# -STM32F1.net
KiCad netlist of a schematic drawn in EasyEDA Pro
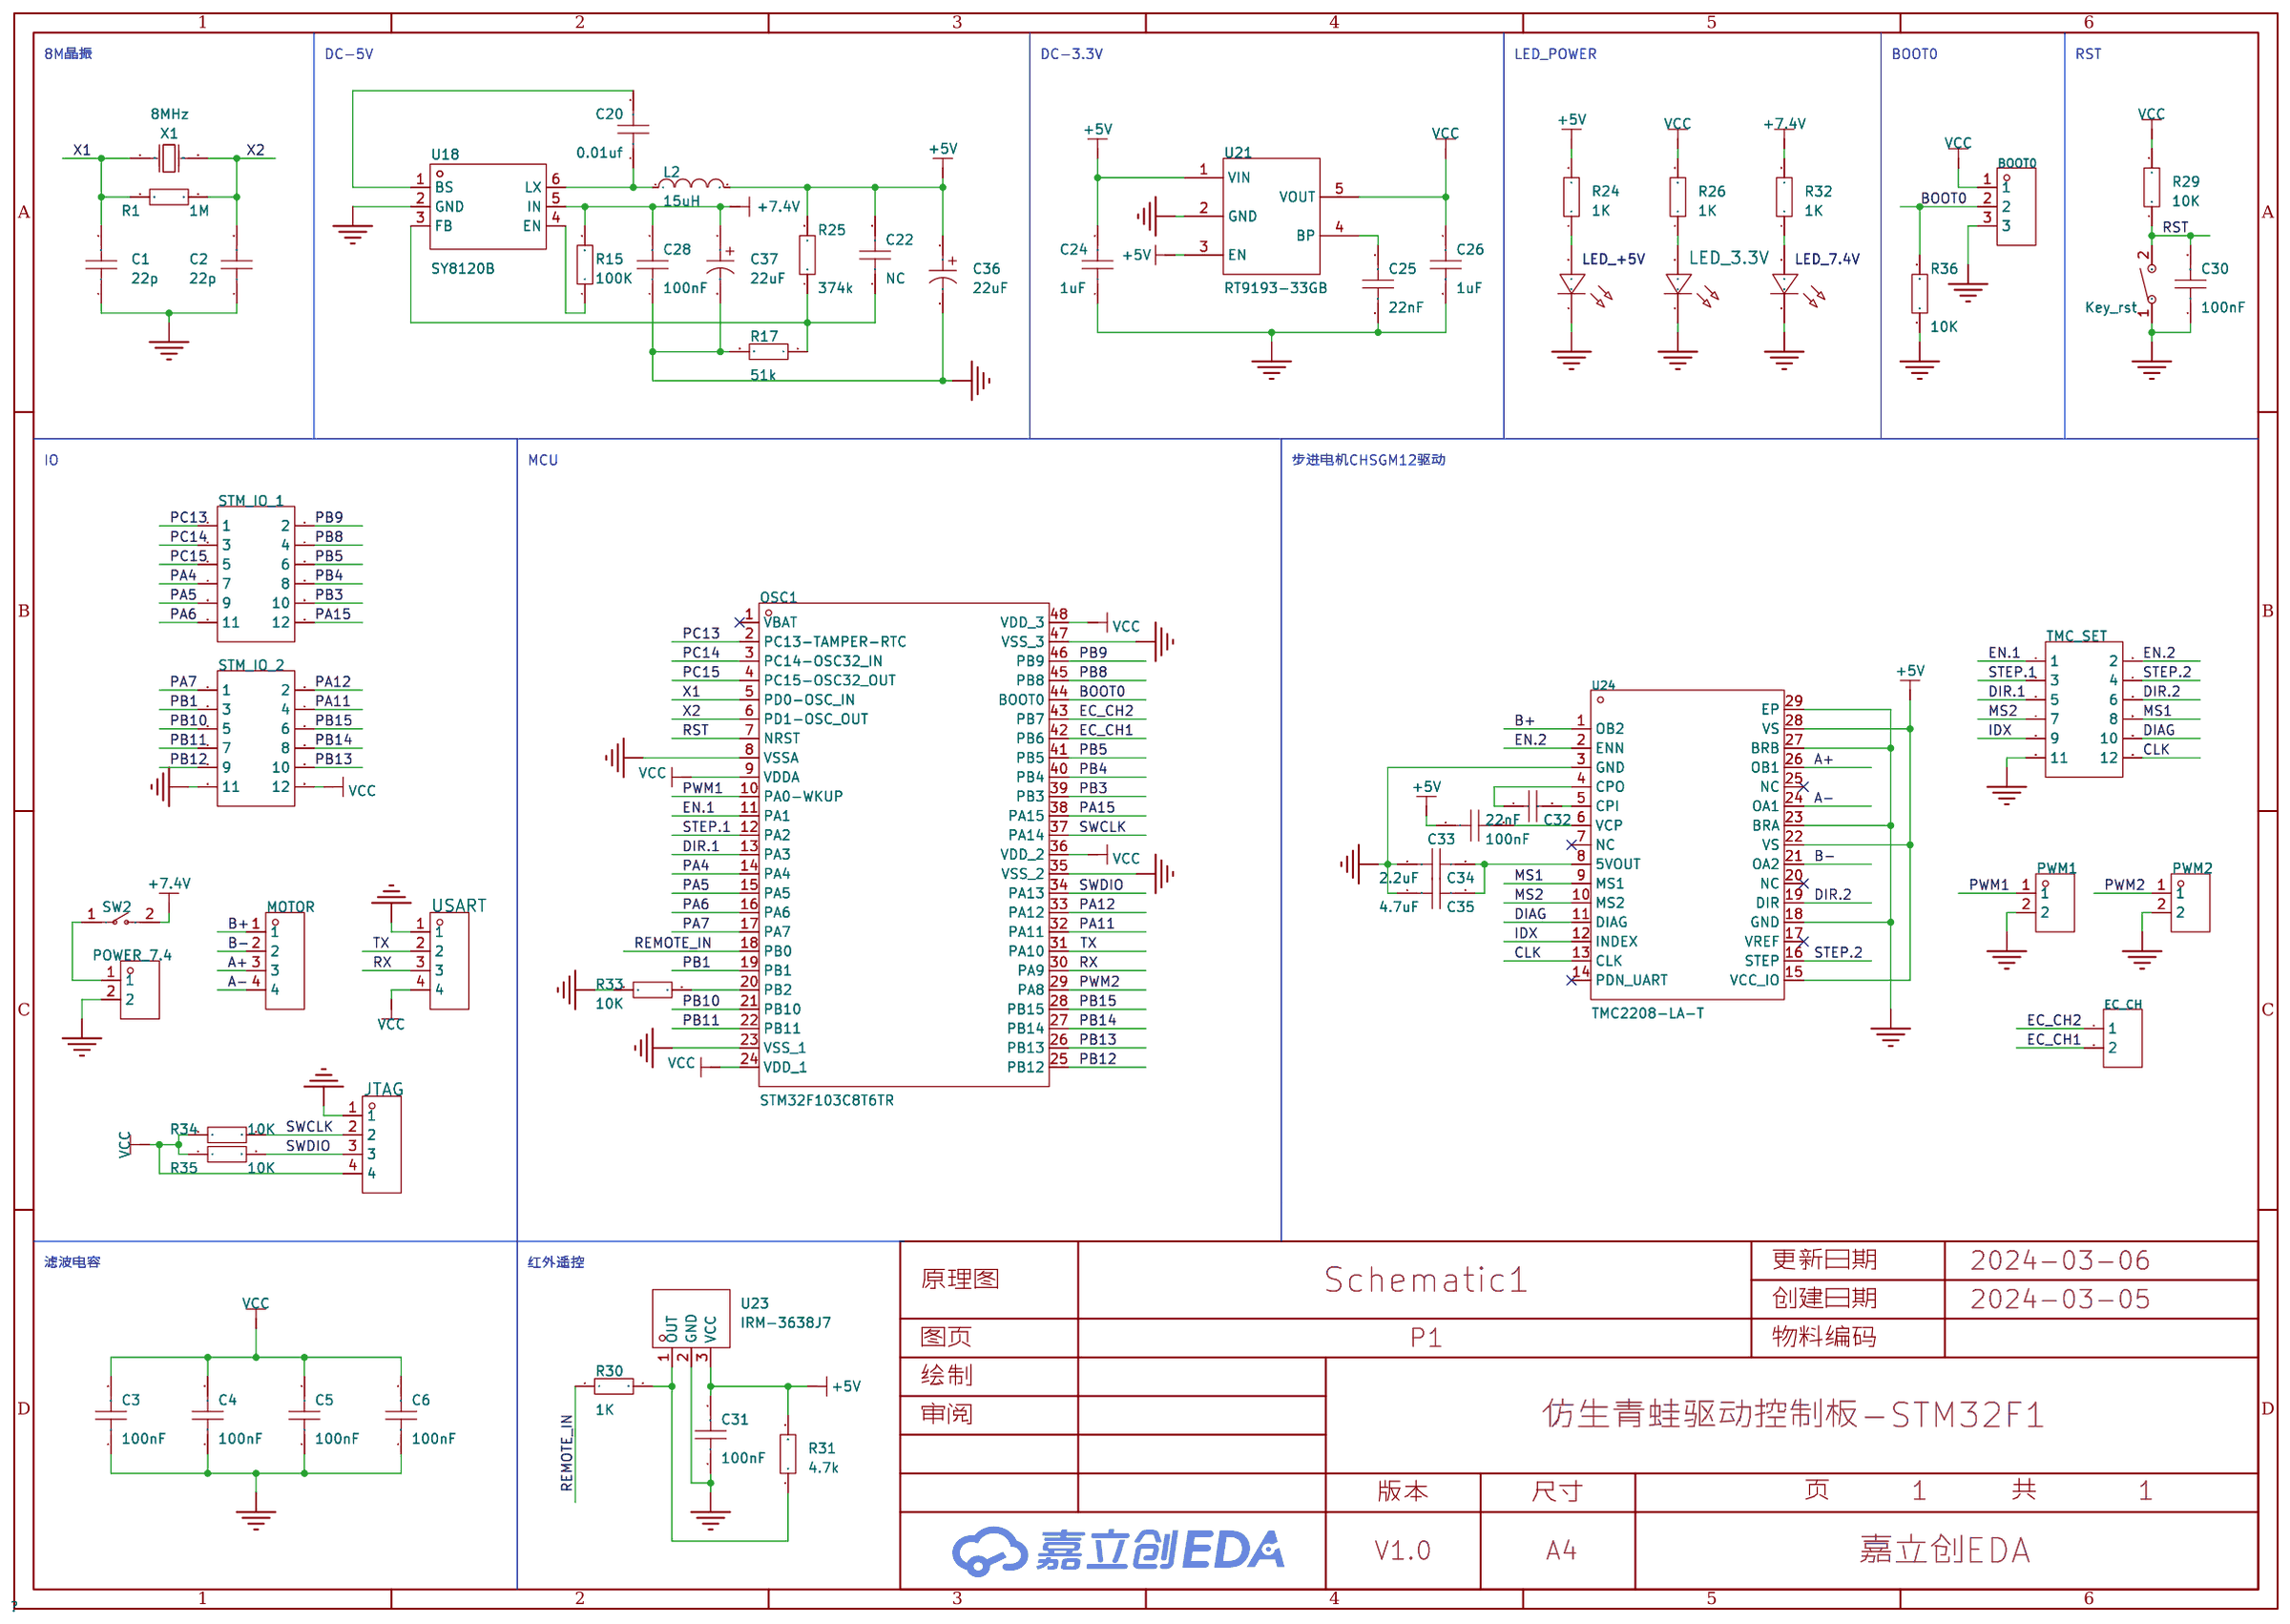
[diagram p0: schematic sheet]

(export (version "E")
  (design (tool "Eeschema 10.0.6"))
  (components
    (comp (ref "BOOT0")
      (value "~")
      (footprint "easyedapro:HDR-TH_3P-P2.54-V-F")
      (libsource (lib "easyedapro") (part "PM254V-11-03-H85"))
    )
    (comp (ref "C1")
      (value "22p")
      (footprint "easyedapro:c0603")
      (libsource (lib "easyedapro") (part "CapAcitance"))
    )
    (comp (ref "C2")
      (value "22p")
      (footprint "easyedapro:c0603")
      (libsource (lib "easyedapro") (part "CapAcitance"))
    )
    (comp (ref "C3")
      (value "100nF")
      (footprint "easyedapro:c0603")
      (libsource (lib "easyedapro") (part "CapAcitance"))
    )
    (comp (ref "C4")
      (value "100nF")
      (footprint "easyedapro:c0603")
      (libsource (lib "easyedapro") (part "CapAcitance"))
    )
    (comp (ref "C5")
      (value "100nF")
      (footprint "easyedapro:c0603")
      (libsource (lib "easyedapro") (part "CapAcitance"))
    )
    (comp (ref "C6")
      (value "100nF")
      (footprint "easyedapro:c0603")
      (libsource (lib "easyedapro") (part "CapAcitance"))
    )
    (comp (ref "C20")
      (value "0.01uf")
      (footprint "easyedapro:C0805")
      (libsource (lib "easyedapro") (part "CapAcitance"))
    )
    (comp (ref "C22")
      (value "NC")
      (footprint "easyedapro:C0805")
      (libsource (lib "easyedapro") (part "CapAcitance"))
    )
    (comp (ref "C24")
      (value "1uF")
      (footprint "easyedapro:c0603")
      (libsource (lib "easyedapro") (part "CapAcitance"))
    )
    (comp (ref "C25")
      (value "22nF")
      (footprint "easyedapro:c0603")
      (libsource (lib "easyedapro") (part "CapAcitance"))
    )
    (comp (ref "C26")
      (value "1uF")
      (footprint "easyedapro:c0603")
      (libsource (lib "easyedapro") (part "CapAcitance"))
    )
    (comp (ref "C28")
      (value "100nF")
      (footprint "easyedapro:c0603")
      (libsource (lib "easyedapro") (part "CapAcitance"))
    )
    (comp (ref "C30")
      (value "100nF")
      (footprint "easyedapro:c0603")
      (libsource (lib "easyedapro") (part "CapAcitance"))
    )
    (comp (ref "C31")
      (value "100nF")
      (footprint "easyedapro:c0603")
      (libsource (lib "easyedapro") (part "CapAcitance"))
    )
    (comp (ref "C32")
      (value "22nF")
      (footprint "easyedapro:c0603")
      (description "容值:22nF;精度:±10%;额定电压:50V;材质(温度系数):X7R;")
      (fields (field (name "Manufacturer Part") "0603B223K500NT") (field (name "Manufacturer") "FH(风华)"))
      (libsource (lib "easyedapro") (part "0603B223K500NT"))
    )
    (comp (ref "C33")
      (value "100nF")
      (footprint "easyedapro:c0603")
      (libsource (lib "easyedapro") (part "CapAcitance"))
    )
    (comp (ref "C34")
      (value "2.2uF")
      (footprint "easyedapro:c0603")
      (libsource (lib "easyedapro") (part "CapAcitance"))
    )
    (comp (ref "C35")
      (value "4.7uF")
      (footprint "easyedapro:c0603")
      (libsource (lib "easyedapro") (part "CapAcitance"))
    )
    (comp (ref "C36")
      (value "22uF")
      (footprint "easyedapro:CAP-SMD_BD5.0-L5.3-W5.3-LS6.0-FD")
      (description "容值:22uF;精度:±20%;额定电压:25V;纹波电流:26mA@120Hz;等效串联电阻:-;")
      (fields
        (field (name "Manufacturer Part") "RVT22UF25V67RV0047")
        (field (name "Manufacturer") "KNSCHA(科尼盛)")
      )
      (libsource (lib "easyedapro") (part "RVT22UF25V67RV0047"))
    )
    (comp (ref "C37")
      (value "22uF")
      (footprint "easyedapro:CAP-SMD_BD5.0-L5.3-W5.3-LS6.0-FD")
      (description "容值:22uF;精度:±20%;额定电压:25V;纹波电流:26mA@120Hz;等效串联电阻:-;")
      (fields
        (field (name "Manufacturer Part") "RVT22UF25V67RV0047")
        (field (name "Manufacturer") "KNSCHA(科尼盛)")
      )
      (libsource (lib "easyedapro") (part "RVT22UF25V67RV0047"))
    )
    (comp (ref "EC_CH")
      (value "~")
      (footprint "easyedapro:HDR-TH_2P-P2.54-V-F")
      (libsource (lib "easyedapro") (part "Header-Female-2.54_1x2"))
    )
    (comp (ref "JTAG")
      (value "~")
      (footprint "easyedapro:HDR-TH_4P-P2.54-V-F")
      (libsource (lib "easyedapro") (part "2.54-1*4P母"))
    )
    (comp (ref "Key_rst")
      (value "TS-1092S-B3D2-G")
      (footprint "easyedapro:SW-SMD_L6.1-W3.6-LS7.9")
      (description "电路结构:单刀单掷;按钮形状:矩形按钮;作用力:250gf;安装方式:立贴;开关长度:6.1mm;开关宽度:3.6mm;开关高度:2.5mm;带支架:不带;机械寿命:-;")
      (fields (field (name "Manufacturer") "Yuandi(元迪)"))
      (libsource (lib "easyedapro") (part "TS-1092S-B3D2-G"))
    )
    (comp (ref "L2")
      (value "15uH")
      (footprint "easyedapro:IND-SMD_L7.0-W6.6_FXL0630")
      (description "电感值:15uH;精度:±20%;额定电流:3A;饱和电流(Isat):4.5A;类型:一体成型电感;")
      (fields (field (name "Manufacturer Part") "FXL0630-150-M") (field (name "Manufacturer") "cjiang(长江微电)"))
      (libsource (lib "easyedapro") (part "FXL0630-150-M"))
    )
    (comp (ref "LED_+5V")
      (value "~")
      (footprint "easyedapro:LED_0603")
      (libsource (lib "easyedapro") (part "LED_G"))
    )
    (comp (ref "LED_3.3V")
      (value "~")
      (footprint "easyedapro:LED_0402")
      (libsource (lib "easyedapro") (part "LED_R"))
    )
    (comp (ref "LED_7.4V")
      (value "~")
      (footprint "easyedapro:LED_0402")
      (libsource (lib "easyedapro") (part "LED_B"))
    )
    (comp (ref "MOTOR")
      (value "ZX-XH2.54-4PZZ")
      (footprint "easyedapro:CONN-TH_4P-P2.50_4PIN")
      (fields (field (name "Manufacturer") "Megastar(兆星)"))
      (libsource (lib "easyedapro") (part "ZX-XH2.54-4PZZ"))
    )
    (comp (ref "OSC1")
      (value "STM32F103C8T6TR")
      (footprint "easyedapro:LQFP-48_L7.0-W7.0-P0.50-LS9.0-BL")
      (description "CPU内核:CM3;程序存储容量:64KB;RAM总容量:20KB;GPIO端口数量:37;工作电压范围:2V~3.6V;CPU最大主频:72MHz;程序存储器类型:-;")
      (fields (field (name "Manufacturer") "ST(意法半导体)"))
      (libsource (lib "easyedapro") (part "STM32F103C8T6TR"))
    )
    (comp (ref "POWER_7.4")
      (value "ZX-XH2.54-2PZZ")
      (footprint "easyedapro:CONN-TH_2P-P2.50_HX25003-2A")
      (fields (field (name "Manufacturer") "Megastar(兆星)"))
      (libsource (lib "easyedapro") (part "ZX-XH2.54-2PZZ"))
    )
    (comp (ref "PWM1")
      (value "ZX-XH2.54-2PZZ")
      (footprint "easyedapro:CONN-TH_2P-P2.50_HX25003-2A")
      (fields (field (name "Manufacturer") "Megastar(兆星)"))
      (libsource (lib "easyedapro") (part "ZX-XH2.54-2PZZ"))
    )
    (comp (ref "PWM2")
      (value "ZX-XH2.54-2PZZ")
      (footprint "easyedapro:CONN-TH_2P-P2.50_HX25003-2A")
      (fields (field (name "Manufacturer") "Megastar(兆星)"))
      (libsource (lib "easyedapro") (part "ZX-XH2.54-2PZZ"))
    )
    (comp (ref "R1") (value "1M") (footprint "easyedapro:r0603") (libsource (lib "easyedapro") (part "电阻")))
    (comp (ref "R15")
      (value "100K")
      (footprint "easyedapro:R0805")
      (libsource (lib "easyedapro") (part "电阻"))
    )
    (comp (ref "R17") (value "51k") (footprint "easyedapro:R0805") (libsource (lib "easyedapro") (part "电阻")))
    (comp (ref "R24") (value "1K") (footprint "easyedapro:R0805") (libsource (lib "easyedapro") (part "电阻")))
    (comp (ref "R25")
      (value "374k")
      (footprint "easyedapro:R0805")
      (libsource (lib "easyedapro") (part "电阻"))
    )
    (comp (ref "R26") (value "1K") (footprint "easyedapro:r0603") (libsource (lib "easyedapro") (part "电阻")))
    (comp (ref "R29") (value "10K") (footprint "easyedapro:r0603") (libsource (lib "easyedapro") (part "电阻")))
    (comp (ref "R30") (value "1K") (footprint "easyedapro:r0603") (libsource (lib "easyedapro") (part "电阻")))
    (comp (ref "R31")
      (value "4.7k")
      (footprint "easyedapro:r0603")
      (libsource (lib "easyedapro") (part "电阻"))
    )
    (comp (ref "R32") (value "1K") (footprint "easyedapro:r0603") (libsource (lib "easyedapro") (part "电阻")))
    (comp (ref "R33") (value "10K") (footprint "easyedapro:r0603") (libsource (lib "easyedapro") (part "电阻")))
    (comp (ref "R34") (value "10K") (footprint "easyedapro:r0603") (libsource (lib "easyedapro") (part "电阻")))
    (comp (ref "R35") (value "10K") (footprint "easyedapro:r0603") (libsource (lib "easyedapro") (part "电阻")))
    (comp (ref "R36") (value "10K") (footprint "easyedapro:r0603") (libsource (lib "easyedapro") (part "电阻")))
    (comp (ref "STM_IO_1")
      (value "~")
      (footprint "easyedapro:HDR-TH_12P-P2.54-V-M-R2-C6-S2.54")
      (libsource (lib "easyedapro") (part "HDR-F-2.54_2x6"))
    )
    (comp (ref "STM_IO_2")
      (value "~")
      (footprint "easyedapro:HDR-TH_12P-P2.54-V-M-R2-C6-S2.54")
      (libsource (lib "easyedapro") (part "HDR-F-2.54_2x6"))
    )
    (comp (ref "SW2")
      (value "KCD11-2P-R")
      (footprint "easyedapro:SW-TH_2P-L15.0-W10.5-P5.00_KCD11-2P-R")
      (description "带灯:无;引脚样式:焊片;额定电流:3A;额定电压(AC):250V;额定电压(DC):-;电路结构:单刀单掷;机械寿命:1万次;")
      (fields (field (name "Manufacturer") "SHOU HAN(首韩)"))
      (libsource (lib "easyedapro") (part "KCD11-2P-R"))
    )
    (comp (ref "TMC_SET")
      (value "~")
      (footprint "easyedapro:HDR-TH_12P-P2.54-V-M-R2-C6-S2.54")
      (libsource (lib "easyedapro") (part "HDR-F-2.54_2x6"))
    )
    (comp (ref "U18")
      (value "SY8120B")
      (footprint "easyedapro:SOT-23-6_L2.9-W1.6-P0.95-LS2.8-BL")
      (fields (field (name "Manufacturer") "Slkor(萨科微)"))
      (libsource (lib "easyedapro") (part "SY8120B"))
    )
    (comp (ref "U21")
      (value "RT9193-33GB")
      (footprint "easyedapro:SOT-23-5_L3.0-W1.7-P0.95-LS2.8-BL")
      (description "输出类型:固定;最大输入电压:5.5V;输出电压:3.3V;最大输出电流:300mA;电源纹波抑制比(PSRR):70dB;输出极性:正极;")
      (fields (field (name "Manufacturer") "RICHTEK(立锜)"))
      (libsource (lib "easyedapro") (part "RT9193-33GB"))
    )
    (comp (ref "U23")
      (value "IRM-3638J7")
      (footprint "easyedapro:OPTO-TH_IRM-3638MF56")
      (description "工作电压:4.5V~5.5V;接收角度:±35°;")
      (fields (field (name "Manufacturer") "EVERLIGHT(亿光)"))
      (libsource (lib "easyedapro") (part "IRM-3638J7"))
    )
    (comp (ref "U24")
      (value "TMC2208-LA-T")
      (footprint "easyedapro:QFN-28_L5.0-W5.0-P0.50-BL-EP")
      (fields (field (name "Manufacturer") "TRINAMIC"))
      (libsource (lib "easyedapro") (part "TMC2208-LA-T"))
    )
    (comp (ref "USART")
      (value "~")
      (footprint "easyedapro:HDR-TH_4P-P2.54-V-F")
      (libsource (lib "easyedapro") (part "2.54-1*4P母"))
    )
    (comp (ref "X1")
      (value "8MHz")
      (footprint "easyedapro:CRYSTAL-SMD_L5.0-W3.2")
      (description "晶振类型:贴片晶振;频率:8MHz;常温频差:±10ppm;外接负载电容:20pF;频率稳定度(全温):±50ppm;")
      (fields (field (name "Manufacturer Part") "X50328MSB2GI") (field (name "Manufacturer") "YXC(扬兴晶振)"))
      (libsource (lib "easyedapro") (part "X50328MSB2GI"))
    )
  )
  (nets
    (net (code "1") (name "+5V") (class "Default")
      (node (ref "C22") (pin "2") (pinfunction "2_2") (pintype "input"))
      (node (ref "C24") (pin "2") (pinfunction "2_2") (pintype "input"))
      (node (ref "C31") (pin "2") (pinfunction "2_2") (pintype "input"))
      (node (ref "C33") (pin "1") (pinfunction "1_1") (pintype "input"))
      (node (ref "C36") (pin "1") (pinfunction "1_1") (pintype "input"))
      (node (ref "L2") (pin "2") (pinfunction "2_2") (pintype "unspecified"))
      (node (ref "R24") (pin "2") (pinfunction "2_2") (pintype "input"))
      (node (ref "R25") (pin "2") (pinfunction "2_2") (pintype "input"))
      (node (ref "R31") (pin "2") (pinfunction "2_2") (pintype "input"))
      (node (ref "U21") (pin "1") (pinfunction "VIN_1") (pintype "unspecified"))
      (node (ref "U21") (pin "3") (pinfunction "EN_3") (pintype "unspecified"))
      (node (ref "U23") (pin "3") (pinfunction "VCC_3") (pintype "unspecified"))
      (node (ref "U24") (pin "15") (pinfunction "VCC_IO_15") (pintype "input"))
      (node (ref "U24") (pin "22") (pinfunction "VS_22") (pintype "input"))
      (node (ref "U24") (pin "28") (pinfunction "VS_28") (pintype "input"))
    )
    (net (code "2") (name "+7.4V") (class "Default")
      (node (ref "C28") (pin "2") (pinfunction "2_2") (pintype "input"))
      (node (ref "C37") (pin "1") (pinfunction "1_1") (pintype "input"))
      (node (ref "R15") (pin "2") (pinfunction "2_2") (pintype "input"))
      (node (ref "R32") (pin "2") (pinfunction "2_2") (pintype "input"))
      (node (ref "SW2") (pin "2") (pinfunction "2_2") (pintype "unspecified"))
      (node (ref "U18") (pin "5") (pinfunction "IN_5") (pintype "unspecified"))
    )
    (net (code "3") (name "/A+") (class "Default")
      (node (ref "MOTOR") (pin "3") (pinfunction "3_3") (pintype "unspecified"))
      (node (ref "U24") (pin "26") (pinfunction "OB1_26") (pintype "input"))
    )
    (net (code "4") (name "/A-") (class "Default")
      (node (ref "MOTOR") (pin "4") (pinfunction "4_4") (pintype "unspecified"))
      (node (ref "U24") (pin "24") (pinfunction "OA1_24") (pintype "input"))
    )
    (net (code "5") (name "/B+") (class "Default")
      (node (ref "MOTOR") (pin "1") (pinfunction "1_1") (pintype "unspecified"))
      (node (ref "U24") (pin "1") (pinfunction "OB2_1") (pintype "input"))
    )
    (net (code "6") (name "/B-") (class "Default")
      (node (ref "MOTOR") (pin "2") (pinfunction "2_2") (pintype "unspecified"))
      (node (ref "U24") (pin "21") (pinfunction "OA2_21") (pintype "input"))
    )
    (net (code "7") (name "/BOOT0") (class "Default")
      (node (ref "BOOT0") (pin "2") (pinfunction "2_2") (pintype "input"))
      (node (ref "OSC1") (pin "44") (pinfunction "BOOT0_44") (pintype "unspecified"))
      (node (ref "R36") (pin "2") (pinfunction "2_2") (pintype "input"))
    )
    (net (code "8") (name "/CLK") (class "Default")
      (node (ref "TMC_SET") (pin "12") (pinfunction "12_12") (pintype "input"))
      (node (ref "U24") (pin "13") (pinfunction "CLK_13") (pintype "input"))
    )
    (net (code "9") (name "/DIAG") (class "Default")
      (node (ref "TMC_SET") (pin "10") (pinfunction "10_10") (pintype "input"))
      (node (ref "U24") (pin "11") (pinfunction "DIAG_11") (pintype "input"))
    )
    (net (code "10") (name "/DIR.1") (class "Default")
      (node (ref "OSC1") (pin "13") (pinfunction "PA3_13") (pintype "unspecified"))
      (node (ref "TMC_SET") (pin "5") (pinfunction "5_5") (pintype "input"))
    )
    (net (code "11") (name "/DIR.2") (class "Default")
      (node (ref "TMC_SET") (pin "6") (pinfunction "6_6") (pintype "input"))
      (node (ref "U24") (pin "19") (pinfunction "DIR_19") (pintype "input"))
    )
    (net (code "12") (name "/EC_CH1") (class "Default")
      (node (ref "EC_CH") (pin "2") (pinfunction "2_2") (pintype "input"))
      (node (ref "OSC1") (pin "42") (pinfunction "PB6_42") (pintype "unspecified"))
    )
    (net (code "13") (name "/EC_CH2") (class "Default")
      (node (ref "EC_CH") (pin "1") (pinfunction "1_1") (pintype "input"))
      (node (ref "OSC1") (pin "43") (pinfunction "PB7_43") (pintype "unspecified"))
    )
    (net (code "14") (name "/EN.1") (class "Default")
      (node (ref "OSC1") (pin "11") (pinfunction "PA1_11") (pintype "unspecified"))
      (node (ref "TMC_SET") (pin "1") (pinfunction "1_1") (pintype "input"))
    )
    (net (code "15") (name "/EN.2") (class "Default")
      (node (ref "TMC_SET") (pin "2") (pinfunction "2_2") (pintype "input"))
      (node (ref "U24") (pin "2") (pinfunction "ENN_2") (pintype "input"))
    )
    (net (code "16") (name "/IDX") (class "Default")
      (node (ref "TMC_SET") (pin "9") (pinfunction "9_9") (pintype "input"))
      (node (ref "U24") (pin "12") (pinfunction "INDEX_12") (pintype "input"))
    )
    (net (code "17") (name "/MS1") (class "Default")
      (node (ref "TMC_SET") (pin "8") (pinfunction "8_8") (pintype "input"))
      (node (ref "U24") (pin "9") (pinfunction "MS1_9") (pintype "input"))
    )
    (net (code "18") (name "/MS2") (class "Default")
      (node (ref "TMC_SET") (pin "7") (pinfunction "7_7") (pintype "input"))
      (node (ref "U24") (pin "10") (pinfunction "MS2_10") (pintype "input"))
    )
    (net (code "19") (name "/PA4") (class "Default")
      (node (ref "OSC1") (pin "14") (pinfunction "PA4_14") (pintype "unspecified"))
      (node (ref "STM_IO_1") (pin "7") (pinfunction "7_7") (pintype "input"))
    )
    (net (code "20") (name "/PA5") (class "Default")
      (node (ref "OSC1") (pin "15") (pinfunction "PA5_15") (pintype "unspecified"))
      (node (ref "STM_IO_1") (pin "9") (pinfunction "9_9") (pintype "input"))
    )
    (net (code "21") (name "/PA6") (class "Default")
      (node (ref "OSC1") (pin "16") (pinfunction "PA6_16") (pintype "unspecified"))
      (node (ref "STM_IO_1") (pin "11") (pinfunction "11_11") (pintype "input"))
    )
    (net (code "22") (name "/PA7") (class "Default")
      (node (ref "OSC1") (pin "17") (pinfunction "PA7_17") (pintype "unspecified"))
      (node (ref "STM_IO_2") (pin "1") (pinfunction "1_1") (pintype "input"))
    )
    (net (code "23") (name "/PA11") (class "Default")
      (node (ref "OSC1") (pin "32") (pinfunction "PA11_32") (pintype "unspecified"))
      (node (ref "STM_IO_2") (pin "4") (pinfunction "4_4") (pintype "input"))
    )
    (net (code "24") (name "/PA12") (class "Default")
      (node (ref "OSC1") (pin "33") (pinfunction "PA12_33") (pintype "unspecified"))
      (node (ref "STM_IO_2") (pin "2") (pinfunction "2_2") (pintype "input"))
    )
    (net (code "25") (name "/PA15") (class "Default")
      (node (ref "OSC1") (pin "38") (pinfunction "PA15_38") (pintype "unspecified"))
      (node (ref "STM_IO_1") (pin "12") (pinfunction "12_12") (pintype "input"))
    )
    (net (code "26") (name "/PB1") (class "Default")
      (node (ref "OSC1") (pin "19") (pinfunction "PB1_19") (pintype "unspecified"))
      (node (ref "STM_IO_2") (pin "3") (pinfunction "3_3") (pintype "input"))
    )
    (net (code "27") (name "/PB3") (class "Default")
      (node (ref "OSC1") (pin "39") (pinfunction "PB3_39") (pintype "unspecified"))
      (node (ref "STM_IO_1") (pin "10") (pinfunction "10_10") (pintype "input"))
    )
    (net (code "28") (name "/PB4") (class "Default")
      (node (ref "OSC1") (pin "40") (pinfunction "PB4_40") (pintype "unspecified"))
      (node (ref "STM_IO_1") (pin "8") (pinfunction "8_8") (pintype "input"))
    )
    (net (code "29") (name "/PB5") (class "Default")
      (node (ref "OSC1") (pin "41") (pinfunction "PB5_41") (pintype "unspecified"))
      (node (ref "STM_IO_1") (pin "6") (pinfunction "6_6") (pintype "input"))
    )
    (net (code "30") (name "/PB8") (class "Default")
      (node (ref "OSC1") (pin "45") (pinfunction "PB8_45") (pintype "unspecified"))
      (node (ref "STM_IO_1") (pin "4") (pinfunction "4_4") (pintype "input"))
    )
    (net (code "31") (name "/PB9") (class "Default")
      (node (ref "OSC1") (pin "46") (pinfunction "PB9_46") (pintype "unspecified"))
      (node (ref "STM_IO_1") (pin "2") (pinfunction "2_2") (pintype "input"))
    )
    (net (code "32") (name "/PB10") (class "Default")
      (node (ref "OSC1") (pin "21") (pinfunction "PB10_21") (pintype "unspecified"))
      (node (ref "STM_IO_2") (pin "5") (pinfunction "5_5") (pintype "input"))
    )
    (net (code "33") (name "/PB11") (class "Default")
      (node (ref "OSC1") (pin "22") (pinfunction "PB11_22") (pintype "unspecified"))
      (node (ref "STM_IO_2") (pin "7") (pinfunction "7_7") (pintype "input"))
    )
    (net (code "34") (name "/PB12") (class "Default")
      (node (ref "OSC1") (pin "25") (pinfunction "PB12_25") (pintype "unspecified"))
      (node (ref "STM_IO_2") (pin "9") (pinfunction "9_9") (pintype "input"))
    )
    (net (code "35") (name "/PB13") (class "Default")
      (node (ref "OSC1") (pin "26") (pinfunction "PB13_26") (pintype "unspecified"))
      (node (ref "STM_IO_2") (pin "10") (pinfunction "10_10") (pintype "input"))
    )
    (net (code "36") (name "/PB14") (class "Default")
      (node (ref "OSC1") (pin "27") (pinfunction "PB14_27") (pintype "unspecified"))
      (node (ref "STM_IO_2") (pin "8") (pinfunction "8_8") (pintype "input"))
    )
    (net (code "37") (name "/PB15") (class "Default")
      (node (ref "OSC1") (pin "28") (pinfunction "PB15_28") (pintype "unspecified"))
      (node (ref "STM_IO_2") (pin "6") (pinfunction "6_6") (pintype "input"))
    )
    (net (code "38") (name "/PC13") (class "Default")
      (node (ref "OSC1") (pin "2") (pinfunction "PC13-TAMPER-RTC_2") (pintype "unspecified"))
      (node (ref "STM_IO_1") (pin "1") (pinfunction "1_1") (pintype "input"))
    )
    (net (code "39") (name "/PC14") (class "Default")
      (node (ref "OSC1") (pin "3") (pinfunction "PC14-OSC32_IN_3") (pintype "unspecified"))
      (node (ref "STM_IO_1") (pin "3") (pinfunction "3_3") (pintype "input"))
    )
    (net (code "40") (name "/PC15") (class "Default")
      (node (ref "OSC1") (pin "4") (pinfunction "PC15-OSC32_OUT_4") (pintype "unspecified"))
      (node (ref "STM_IO_1") (pin "5") (pinfunction "5_5") (pintype "input"))
    )
    (net (code "41") (name "/PWM1") (class "Default")
      (node (ref "OSC1") (pin "10") (pinfunction "PA0-WKUP_10") (pintype "unspecified"))
      (node (ref "PWM1") (pin "1") (pinfunction "1_1") (pintype "unspecified"))
    )
    (net (code "42") (name "/PWM2") (class "Default")
      (node (ref "OSC1") (pin "29") (pinfunction "PA8_29") (pintype "unspecified"))
      (node (ref "PWM2") (pin "1") (pinfunction "1_1") (pintype "unspecified"))
    )
    (net (code "43") (name "/REMOTE_IN") (class "Default")
      (node (ref "OSC1") (pin "18") (pinfunction "PB0_18") (pintype "unspecified"))
      (node (ref "R30") (pin "1") (pinfunction "1_1") (pintype "input"))
    )
    (net (code "44") (name "/RST") (class "Default")
      (node (ref "C30") (pin "2") (pinfunction "2_2") (pintype "input"))
      (node (ref "Key_rst") (pin "2") (pinfunction "2_2") (pintype "unspecified"))
      (node (ref "OSC1") (pin "7") (pinfunction "NRST_7") (pintype "unspecified"))
      (node (ref "R29") (pin "1") (pinfunction "1_1") (pintype "input"))
    )
    (net (code "45") (name "/RX") (class "Default")
      (node (ref "OSC1") (pin "30") (pinfunction "PA9_30") (pintype "unspecified"))
      (node (ref "USART") (pin "3") (pinfunction "3_3") (pintype "input"))
    )
    (net (code "46") (name "/STEP.1") (class "Default")
      (node (ref "OSC1") (pin "12") (pinfunction "PA2_12") (pintype "unspecified"))
      (node (ref "TMC_SET") (pin "3") (pinfunction "3_3") (pintype "input"))
    )
    (net (code "47") (name "/STEP.2") (class "Default")
      (node (ref "TMC_SET") (pin "4") (pinfunction "4_4") (pintype "input"))
      (node (ref "U24") (pin "16") (pinfunction "STEP_16") (pintype "input"))
    )
    (net (code "48") (name "/SWCLK") (class "Default")
      (node (ref "JTAG") (pin "2") (pinfunction "2_2") (pintype "input"))
      (node (ref "OSC1") (pin "37") (pinfunction "PA14_37") (pintype "unspecified"))
      (node (ref "R34") (pin "2") (pinfunction "2_2") (pintype "input"))
    )
    (net (code "49") (name "/SWDIO") (class "Default")
      (node (ref "JTAG") (pin "3") (pinfunction "3_3") (pintype "input"))
      (node (ref "OSC1") (pin "34") (pinfunction "PA13_34") (pintype "unspecified"))
      (node (ref "R35") (pin "2") (pinfunction "2_2") (pintype "input"))
    )
    (net (code "50") (name "/TX") (class "Default")
      (node (ref "OSC1") (pin "31") (pinfunction "PA10_31") (pintype "unspecified"))
      (node (ref "USART") (pin "2") (pinfunction "2_2") (pintype "input"))
    )
    (net (code "51") (name "/X1") (class "Default")
      (node (ref "C1") (pin "2") (pinfunction "2_2") (pintype "input"))
      (node (ref "OSC1") (pin "5") (pinfunction "PD0-OSC_IN_5") (pintype "unspecified"))
      (node (ref "R1") (pin "1") (pinfunction "1_1") (pintype "input"))
      (node (ref "X1") (pin "1") (pinfunction "OSC1_1") (pintype "input"))
    )
    (net (code "52") (name "/X2") (class "Default")
      (node (ref "C2") (pin "2") (pinfunction "2_2") (pintype "input"))
      (node (ref "OSC1") (pin "6") (pinfunction "PD1-OSC_OUT_6") (pintype "unspecified"))
      (node (ref "R1") (pin "2") (pinfunction "2_2") (pintype "input"))
      (node (ref "X1") (pin "2") (pinfunction "OSC2_2") (pintype "input"))
    )
    (net (code "53") (name "GND") (class "Default")
      (node (ref "BOOT0") (pin "3") (pinfunction "3_3") (pintype "input"))
      (node (ref "C1") (pin "1") (pinfunction "1_1") (pintype "input"))
      (node (ref "C2") (pin "1") (pinfunction "1_1") (pintype "input"))
      (node (ref "C24") (pin "1") (pinfunction "1_1") (pintype "input"))
      (node (ref "C25") (pin "2") (pinfunction "2_2") (pintype "input"))
      (node (ref "C26") (pin "2") (pinfunction "2_2") (pintype "input"))
      (node (ref "C28") (pin "1") (pinfunction "1_1") (pintype "input"))
      (node (ref "C3") (pin "1") (pinfunction "1_1") (pintype "input"))
      (node (ref "C30") (pin "1") (pinfunction "1_1") (pintype "input"))
      (node (ref "C31") (pin "1") (pinfunction "1_1") (pintype "input"))
      (node (ref "C34") (pin "1") (pinfunction "1_1") (pintype "input"))
      (node (ref "C35") (pin "1") (pinfunction "1_1") (pintype "input"))
      (node (ref "C36") (pin "2") (pinfunction "2_2") (pintype "input"))
      (node (ref "C37") (pin "2") (pinfunction "2_2") (pintype "input"))
      (node (ref "C4") (pin "1") (pinfunction "1_1") (pintype "input"))
      (node (ref "C5") (pin "1") (pinfunction "1_1") (pintype "input"))
      (node (ref "C6") (pin "1") (pinfunction "1_1") (pintype "input"))
      (node (ref "JTAG") (pin "1") (pinfunction "1_1") (pintype "input"))
      (node (ref "Key_rst") (pin "1") (pinfunction "1_1") (pintype "unspecified"))
      (node (ref "LED_+5V") (pin "1") (pinfunction "C_1") (pintype "input"))
      (node (ref "LED_3.3V") (pin "1") (pinfunction "C_1") (pintype "input"))
      (node (ref "LED_7.4V") (pin "1") (pinfunction "C_1") (pintype "input"))
      (node (ref "OSC1") (pin "23") (pinfunction "VSS_1_23") (pintype "unspecified"))
      (node (ref "OSC1") (pin "35") (pinfunction "VSS_2_35") (pintype "unspecified"))
      (node (ref "OSC1") (pin "47") (pinfunction "VSS_3_47") (pintype "unspecified"))
      (node (ref "OSC1") (pin "8") (pinfunction "VSSA_8") (pintype "unspecified"))
      (node (ref "POWER_7.4") (pin "2") (pinfunction "2_2") (pintype "unspecified"))
      (node (ref "PWM1") (pin "2") (pinfunction "2_2") (pintype "unspecified"))
      (node (ref "PWM2") (pin "2") (pinfunction "2_2") (pintype "unspecified"))
      (node (ref "R17") (pin "2") (pinfunction "2_2") (pintype "input"))
      (node (ref "R33") (pin "1") (pinfunction "1_1") (pintype "input"))
      (node (ref "R36") (pin "1") (pinfunction "1_1") (pintype "input"))
      (node (ref "STM_IO_2") (pin "11") (pinfunction "11_11") (pintype "input"))
      (node (ref "TMC_SET") (pin "11") (pinfunction "11_11") (pintype "input"))
      (node (ref "U18") (pin "2") (pinfunction "GND_2") (pintype "unspecified"))
      (node (ref "U21") (pin "2") (pinfunction "GND_2") (pintype "unspecified"))
      (node (ref "U23") (pin "2") (pinfunction "GND_2") (pintype "unspecified"))
      (node (ref "U24") (pin "18") (pinfunction "GND_18") (pintype "input"))
      (node (ref "U24") (pin "23") (pinfunction "BRA_23") (pintype "input"))
      (node (ref "U24") (pin "27") (pinfunction "BRB_27") (pintype "input"))
      (node (ref "U24") (pin "29") (pinfunction "EP_29") (pintype "input"))
      (node (ref "U24") (pin "3") (pinfunction "GND_3") (pintype "input"))
      (node (ref "USART") (pin "1") (pinfunction "1_1") (pintype "input"))
    )
    (net (code "54") (name "Net-(LED_+5V-A)") (class "Default")
      (node (ref "LED_+5V") (pin "2") (pinfunction "A_2") (pintype "input"))
      (node (ref "R24") (pin "1") (pinfunction "1_1") (pintype "input"))
    )
    (net (code "55") (name "Net-(LED_3.3V-A)") (class "Default")
      (node (ref "LED_3.3V") (pin "2") (pinfunction "A_2") (pintype "input"))
      (node (ref "R26") (pin "1") (pinfunction "1_1") (pintype "input"))
    )
    (net (code "56") (name "Net-(LED_7.4V-A)") (class "Default")
      (node (ref "LED_7.4V") (pin "2") (pinfunction "A_2") (pintype "input"))
      (node (ref "R32") (pin "1") (pinfunction "1_1") (pintype "input"))
    )
    (net (code "57") (name "Net-(OSC1-PB2)") (class "Default")
      (node (ref "OSC1") (pin "20") (pinfunction "PB2_20") (pintype "unspecified"))
      (node (ref "R33") (pin "2") (pinfunction "2_2") (pintype "input"))
    )
    (net (code "58") (name "Net-(POWER_7.4-Pad1)") (class "Default")
      (node (ref "POWER_7.4") (pin "1") (pinfunction "1_1") (pintype "unspecified"))
      (node (ref "SW2") (pin "1") (pinfunction "1_1") (pintype "unspecified"))
    )
    (net (code "59") (name "Net-(U18-BS)") (class "Default")
      (node (ref "C20") (pin "2") (pinfunction "2_2") (pintype "input"))
      (node (ref "U18") (pin "1") (pinfunction "BS_1") (pintype "unspecified"))
    )
    (net (code "60") (name "Net-(U18-EN)") (class "Default")
      (node (ref "R15") (pin "1") (pinfunction "1_1") (pintype "input"))
      (node (ref "U18") (pin "4") (pinfunction "EN_4") (pintype "unspecified"))
    )
    (net (code "61") (name "Net-(U18-FB)") (class "Default")
      (node (ref "C22") (pin "1") (pinfunction "1_1") (pintype "input"))
      (node (ref "R17") (pin "1") (pinfunction "1_1") (pintype "input"))
      (node (ref "R25") (pin "1") (pinfunction "1_1") (pintype "input"))
      (node (ref "U18") (pin "3") (pinfunction "FB_3") (pintype "unspecified"))
    )
    (net (code "62") (name "Net-(U18-LX)") (class "Default")
      (node (ref "C20") (pin "1") (pinfunction "1_1") (pintype "input"))
      (node (ref "L2") (pin "1") (pinfunction "1_1") (pintype "unspecified"))
      (node (ref "U18") (pin "6") (pinfunction "LX_6") (pintype "unspecified"))
    )
    (net (code "63") (name "Net-(U21-BP)") (class "Default")
      (node (ref "C25") (pin "1") (pinfunction "1_1") (pintype "input"))
      (node (ref "U21") (pin "4") (pinfunction "BP_4") (pintype "unspecified"))
    )
    (net (code "64") (name "Net-(U23-OUT)") (class "Default")
      (node (ref "R30") (pin "2") (pinfunction "2_2") (pintype "input"))
      (node (ref "R31") (pin "1") (pinfunction "1_1") (pintype "input"))
      (node (ref "U23") (pin "1") (pinfunction "OUT_1") (pintype "unspecified"))
    )
    (net (code "65") (name "Net-(U24-5VOUT)") (class "Default")
      (node (ref "C34") (pin "2") (pinfunction "2_2") (pintype "input"))
      (node (ref "C35") (pin "2") (pinfunction "2_2") (pintype "input"))
      (node (ref "U24") (pin "8") (pinfunction "5VOUT_8") (pintype "input"))
    )
    (net (code "66") (name "Net-(U24-CPI)") (class "Default")
      (node (ref "C32") (pin "2") (pinfunction "2_2") (pintype "input"))
      (node (ref "U24") (pin "5") (pinfunction "CPI_5") (pintype "input"))
    )
    (net (code "67") (name "Net-(U24-CPO)") (class "Default")
      (node (ref "C32") (pin "1") (pinfunction "1_1") (pintype "input"))
      (node (ref "U24") (pin "4") (pinfunction "CPO_4") (pintype "input"))
    )
    (net (code "68") (name "Net-(U24-VCP)") (class "Default")
      (node (ref "C33") (pin "2") (pinfunction "2_2") (pintype "input"))
      (node (ref "U24") (pin "6") (pinfunction "VCP_6") (pintype "input"))
    )
    (net (code "69") (name "VCC") (class "Default")
      (node (ref "BOOT0") (pin "1") (pinfunction "1_1") (pintype "input"))
      (node (ref "C26") (pin "1") (pinfunction "1_1") (pintype "input"))
      (node (ref "C3") (pin "2") (pinfunction "2_2") (pintype "input"))
      (node (ref "C4") (pin "2") (pinfunction "2_2") (pintype "input"))
      (node (ref "C5") (pin "2") (pinfunction "2_2") (pintype "input"))
      (node (ref "C6") (pin "2") (pinfunction "2_2") (pintype "input"))
      (node (ref "JTAG") (pin "4") (pinfunction "4_4") (pintype "input"))
      (node (ref "OSC1") (pin "24") (pinfunction "VDD_1_24") (pintype "unspecified"))
      (node (ref "OSC1") (pin "36") (pinfunction "VDD_2_36") (pintype "unspecified"))
      (node (ref "OSC1") (pin "48") (pinfunction "VDD_3_48") (pintype "unspecified"))
      (node (ref "OSC1") (pin "9") (pinfunction "VDDA_9") (pintype "unspecified"))
      (node (ref "R26") (pin "2") (pinfunction "2_2") (pintype "input"))
      (node (ref "R29") (pin "2") (pinfunction "2_2") (pintype "input"))
      (node (ref "R34") (pin "1") (pinfunction "1_1") (pintype "input"))
      (node (ref "R35") (pin "1") (pinfunction "1_1") (pintype "input"))
      (node (ref "STM_IO_2") (pin "12") (pinfunction "12_12") (pintype "input"))
      (node (ref "U21") (pin "5") (pinfunction "VOUT_5") (pintype "unspecified"))
      (node (ref "USART") (pin "4") (pinfunction "4_4") (pintype "input"))
    )
    (net (code "70") (name "unconnected-(OSC1-VBAT-Pad1)") (class "Default")
      (node (ref "OSC1") (pin "1") (pinfunction "VBAT_1") (pintype "unspecified+no_connect"))
    )
    (net (code "71") (name "unconnected-(U24-NC-Pad7)") (class "Default")
      (node (ref "U24") (pin "7") (pinfunction "NC_7") (pintype "input+no_connect"))
    )
    (net (code "72") (name "unconnected-(U24-NC-Pad20)") (class "Default")
      (node (ref "U24") (pin "20") (pinfunction "NC_20") (pintype "input+no_connect"))
    )
    (net (code "73") (name "unconnected-(U24-NC-Pad25)") (class "Default")
      (node (ref "U24") (pin "25") (pinfunction "NC_25") (pintype "input+no_connect"))
    )
    (net (code "74") (name "unconnected-(U24-PDN_UART-Pad14)") (class "Default")
      (node (ref "U24") (pin "14") (pinfunction "PDN_UART_14") (pintype "input+no_connect"))
    )
    (net (code "75") (name "unconnected-(U24-VREF-Pad17)") (class "Default")
      (node (ref "U24") (pin "17") (pinfunction "VREF_17") (pintype "input+no_connect"))
    )
  )
)
